# ATtiny85_and_DRV8830_Combo_--_v04.net
KiCad netlist of a schematic drawn in EAGLE
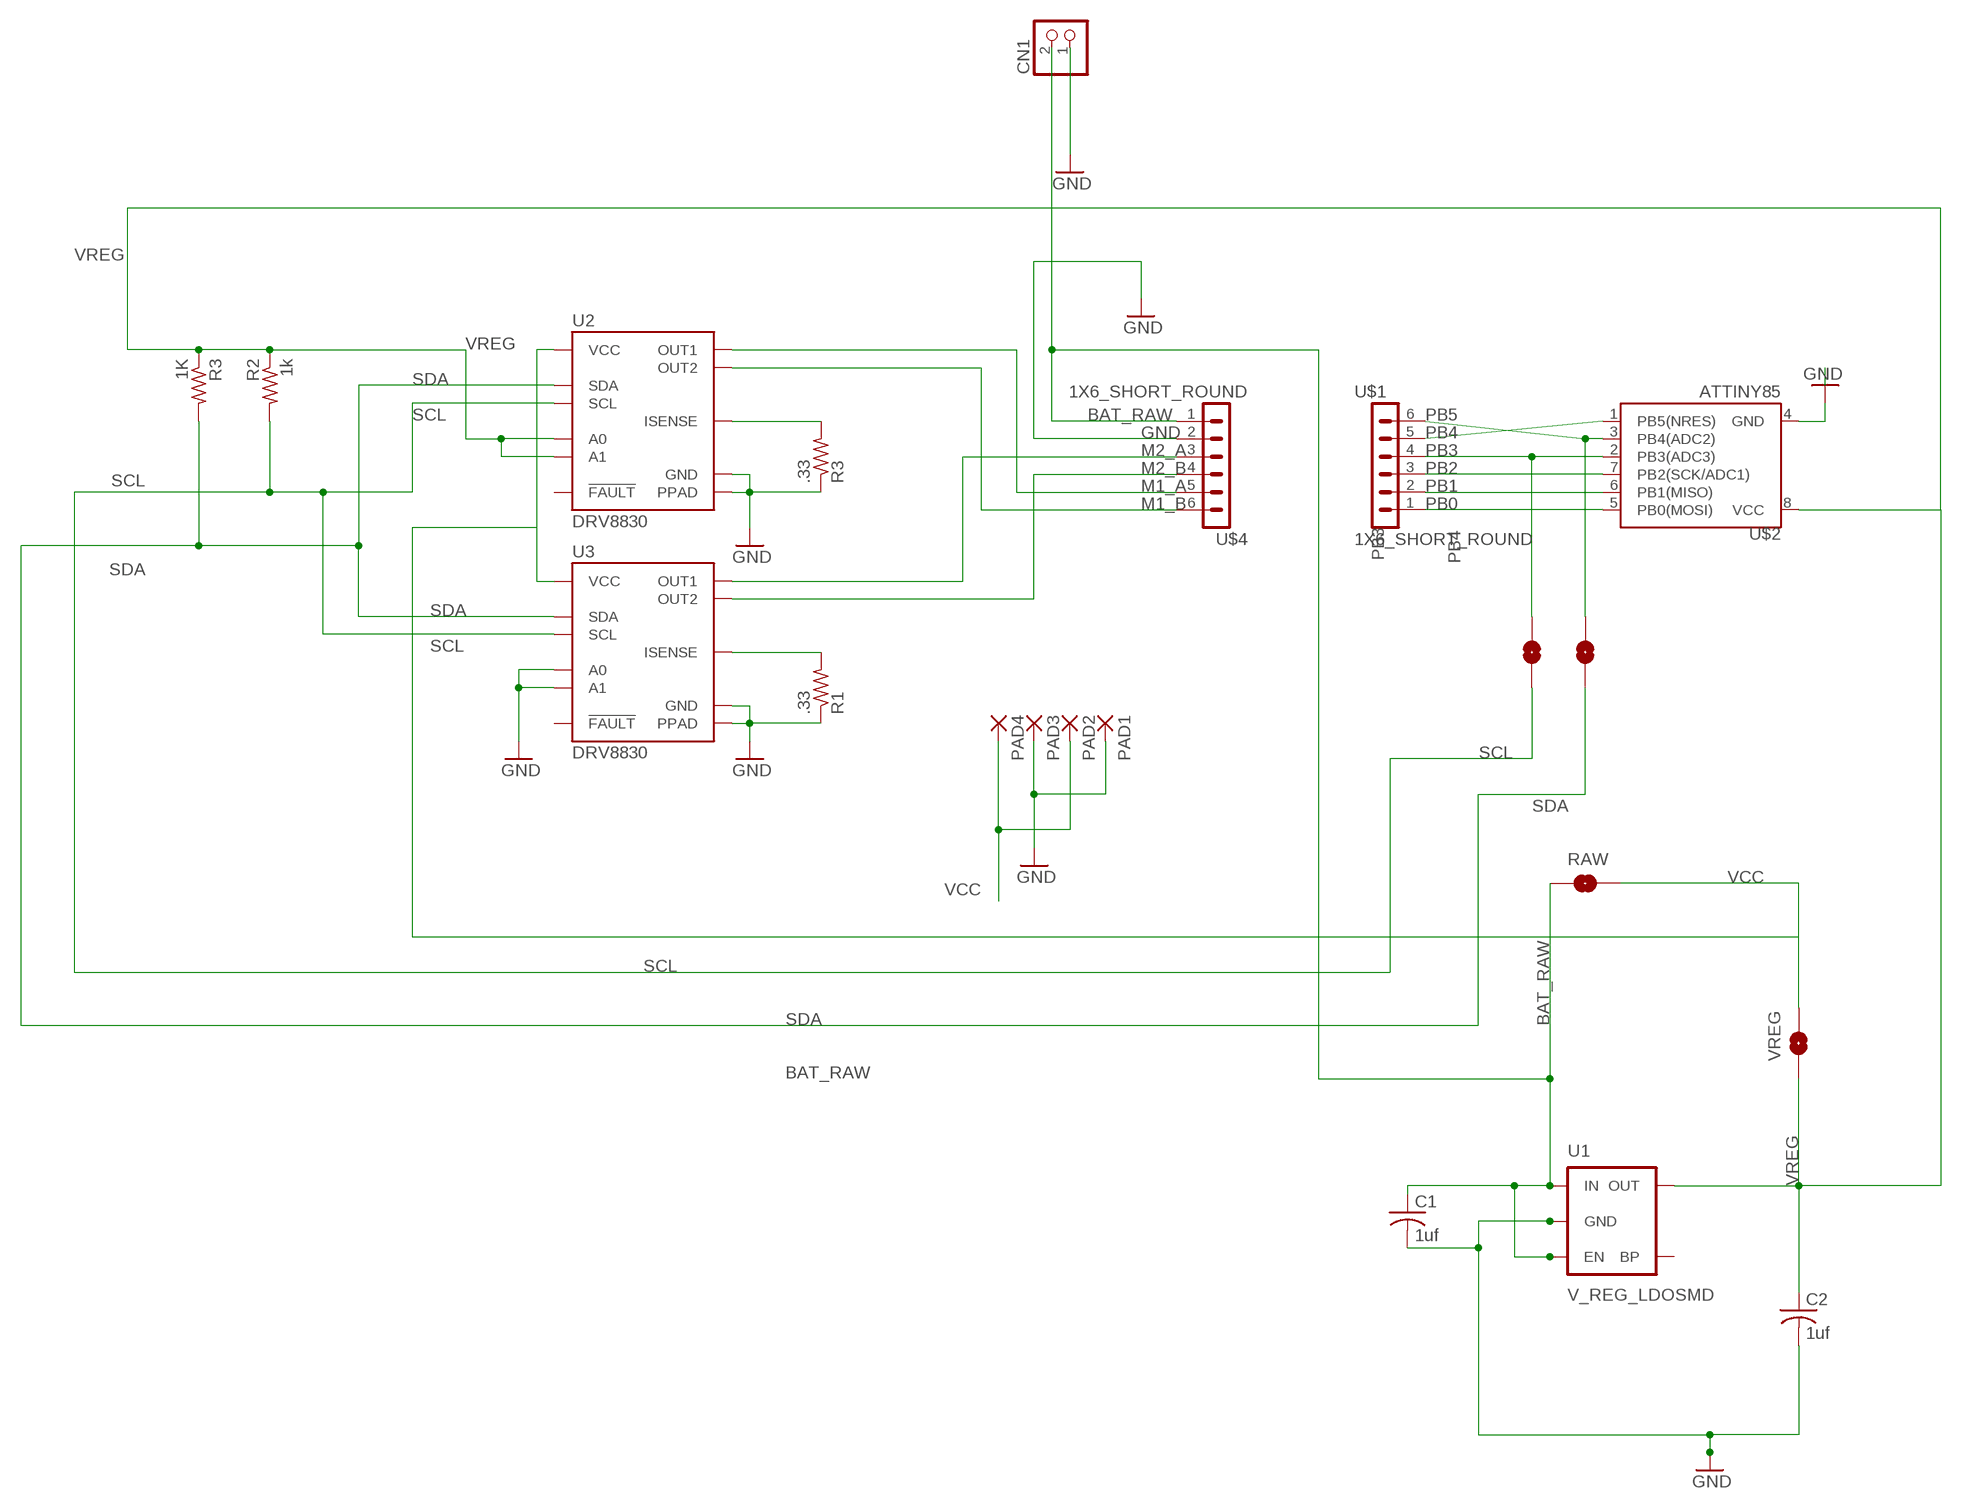
[diagram p0: schematic, sheet 1]

(export (version "E")
  (design (tool "Eeschema 10.0.6"))
  (components
    (comp (ref "1K")
      (value "R3")
      (footprint "eagle-import:R0402")
      (libsource (lib "eagle-import") (part "R-US_R0402"))
    )
    (comp (ref "C1")
      (value "1uf")
      (footprint "eagle-import:C0402")
      (libsource (lib "eagle-import") (part "C-USC0402"))
    )
    (comp (ref "C2")
      (value "1uf")
      (footprint "eagle-import:C0402")
      (libsource (lib "eagle-import") (part "C-USC0402"))
    )
    (comp (ref "CN1")
      (value "JST_2PIN-THM")
      (footprint "eagle-import:JST-PH-2-THM")
      (libsource (lib "eagle-import") (part "JST_2PIN-THM"))
    )
    (comp (ref "PAD1")
      (value "SMD2")
      (footprint "eagle-import:SMD1,27-2,54")
      (libsource (lib "eagle-import") (part "SMD2"))
    )
    (comp (ref "PAD2")
      (value "SMD2")
      (footprint "eagle-import:SMD1,27-2,54")
      (libsource (lib "eagle-import") (part "SMD2"))
    )
    (comp (ref "PAD3")
      (value "SMD2")
      (footprint "eagle-import:SMD1,27-2,54")
      (libsource (lib "eagle-import") (part "SMD2"))
    )
    (comp (ref "PAD4")
      (value "SMD2")
      (footprint "eagle-import:SMD1,27-2,54")
      (libsource (lib "eagle-import") (part "SMD2"))
    )
    (comp (ref "R1")
      (value ".33")
      (footprint "eagle-import:R0402")
      (libsource (lib "eagle-import") (part "R-US_R0402"))
    )
    (comp (ref "R2")
      (value "1k")
      (footprint "eagle-import:R0402")
      (libsource (lib "eagle-import") (part "R-US_R0402"))
    )
    (comp (ref "R3")
      (value ".33")
      (footprint "eagle-import:R0402")
      (libsource (lib "eagle-import") (part "R-US_R0402"))
    )
    (comp (ref "RAW")
      (value "SOLDERJUMPERNO")
      (footprint "eagle-import:SJ_2S-NO")
      (libsource (lib "eagle-import") (part "SOLDERJUMPERNO"))
    )
    (comp (ref "SJ6")
      (value "SOLDERJUMPERNO")
      (footprint "eagle-import:SJ_2S-NO")
      (libsource (lib "eagle-import") (part "SOLDERJUMPERNO"))
    )
    (comp (ref "SJ7")
      (value "SOLDERJUMPERNO")
      (footprint "eagle-import:SJ_2S-NO")
      (libsource (lib "eagle-import") (part "SOLDERJUMPERNO"))
    )
    (comp (ref "U$1")
      (value "1X6_SHORT_ROUND")
      (footprint "eagle-import:1X6_SHORT_ROUND")
      (libsource (lib "eagle-import") (part "1X6_SHORT_ROUND"))
    )
    (comp (ref "U$2")
      (value "ATTINY85")
      (footprint "eagle-import:SO08-EIAJ")
      (libsource (lib "eagle-import") (part "ATTINY45"))
    )
    (comp (ref "U$4")
      (value "1X6_SHORT_ROUND")
      (footprint "eagle-import:1X6_SHORT_ROUND")
      (libsource (lib "eagle-import") (part "1X6_SHORT_ROUND"))
    )
    (comp (ref "U1")
      (value "V_REG_LDOSMD")
      (footprint "eagle-import:SOT23-5")
      (libsource (lib "eagle-import") (part "V_REG_LDOSMD"))
    )
    (comp (ref "U2")
      (value "DRV8830")
      (footprint "eagle-import:MSOP-10-GNDPAD")
      (libsource (lib "eagle-import") (part "DRV8830"))
    )
    (comp (ref "U3")
      (value "DRV8830")
      (footprint "eagle-import:MSOP-10-GNDPAD")
      (libsource (lib "eagle-import") (part "DRV8830"))
    )
    (comp (ref "VREG")
      (value "SOLDERJUMPERNO")
      (footprint "eagle-import:SJ_2S-NO")
      (libsource (lib "eagle-import") (part "SOLDERJUMPERNO"))
    )
  )
  (nets
    (net (code "1") (name "/BAT_RAW") (class "Default")
      (node (ref "C1") (pin "1") (pinfunction "1_1") (pintype "passive"))
      (node (ref "CN1") (pin "2") (pinfunction "1_2") (pintype "passive"))
      (node (ref "RAW") (pin "1") (pinfunction "1_1") (pintype "passive"))
      (node (ref "U$4") (pin "1") (pinfunction "1_1") (pintype "passive"))
      (node (ref "U1") (pin "1") (pinfunction "IN_1") (pintype "input"))
      (node (ref "U1") (pin "3") (pinfunction "EN_3") (pintype "input"))
    )
    (net (code "2") (name "/M1_A") (class "Default")
      (node (ref "U$4") (pin "5") (pinfunction "5_5") (pintype "passive"))
      (node (ref "U2") (pin "3") (pinfunction "OUT1_3") (pintype "power_in"))
    )
    (net (code "3") (name "/M1_B") (class "Default")
      (node (ref "U$4") (pin "6") (pinfunction "6_6") (pintype "passive"))
      (node (ref "U2") (pin "1") (pinfunction "OUT2_1") (pintype "power_in"))
    )
    (net (code "4") (name "/M2_A") (class "Default")
      (node (ref "U$4") (pin "3") (pinfunction "3_3") (pintype "passive"))
      (node (ref "U3") (pin "3") (pinfunction "OUT1_3") (pintype "power_in"))
    )
    (net (code "5") (name "/M2_B") (class "Default")
      (node (ref "U$4") (pin "4") (pinfunction "4_4") (pintype "passive"))
      (node (ref "U3") (pin "1") (pinfunction "OUT2_1") (pintype "power_in"))
    )
    (net (code "6") (name "/PB0") (class "Default")
      (node (ref "U$1") (pin "1") (pinfunction "1_1") (pintype "passive"))
      (node (ref "U$2") (pin "5") (pinfunction "PB0(MOSI)_5") (pintype "bidirectional"))
    )
    (net (code "7") (name "/PB1") (class "Default")
      (node (ref "U$1") (pin "2") (pinfunction "2_2") (pintype "passive"))
      (node (ref "U$2") (pin "6") (pinfunction "PB1(MISO)_6") (pintype "bidirectional"))
    )
    (net (code "8") (name "/PB2") (class "Default")
      (node (ref "U$1") (pin "3") (pinfunction "3_3") (pintype "passive"))
      (node (ref "U$2") (pin "7") (pinfunction "PB2(SCK/ADC1)_7") (pintype "bidirectional"))
    )
    (net (code "9") (name "/PB3") (class "Default")
      (node (ref "SJ7") (pin "2") (pinfunction "2_2") (pintype "passive"))
      (node (ref "U$1") (pin "4") (pinfunction "4_4") (pintype "passive"))
      (node (ref "U$2") (pin "2") (pinfunction "PB3(ADC3)_2") (pintype "bidirectional"))
    )
    (net (code "10") (name "/PB4") (class "Default")
      (node (ref "SJ6") (pin "2") (pinfunction "2_2") (pintype "passive"))
      (node (ref "U$1") (pin "6") (pinfunction "6_6") (pintype "passive"))
      (node (ref "U$2") (pin "3") (pinfunction "PB4(ADC2)_3") (pintype "bidirectional"))
    )
    (net (code "11") (name "/PB5") (class "Default")
      (node (ref "U$1") (pin "5") (pinfunction "5_5") (pintype "passive"))
      (node (ref "U$2") (pin "1") (pinfunction "PB5(NRES)_1") (pintype "bidirectional"))
    )
    (net (code "12") (name "/SCL") (class "Default")
      (node (ref "R2") (pin "2") (pinfunction "2_2") (pintype "passive"))
      (node (ref "SJ7") (pin "1") (pinfunction "1_1") (pintype "passive"))
      (node (ref "U2") (pin "10") (pinfunction "SCL_10") (pintype "input"))
      (node (ref "U3") (pin "10") (pinfunction "SCL_10") (pintype "input"))
    )
    (net (code "13") (name "/SDA") (class "Default")
      (node (ref "1K") (pin "2") (pinfunction "2_2") (pintype "passive"))
      (node (ref "SJ6") (pin "1") (pinfunction "1_1") (pintype "passive"))
      (node (ref "U2") (pin "9") (pinfunction "SDA_9") (pintype "bidirectional"))
      (node (ref "U3") (pin "9") (pinfunction "SDA_9") (pintype "bidirectional"))
    )
    (net (code "14") (name "/VCC") (class "Default")
      (node (ref "PAD2") (pin "1") (pinfunction "P_1") (pintype "passive"))
      (node (ref "PAD4") (pin "1") (pinfunction "P_1") (pintype "passive"))
      (node (ref "RAW") (pin "2") (pinfunction "2_2") (pintype "passive"))
      (node (ref "U2") (pin "4") (pinfunction "VCC_4") (pintype "power_in"))
      (node (ref "U3") (pin "4") (pinfunction "VCC_4") (pintype "power_in"))
      (node (ref "VREG") (pin "2") (pinfunction "2_2") (pintype "passive"))
    )
    (net (code "15") (name "/VREG") (class "Default")
      (node (ref "1K") (pin "1") (pinfunction "1_1") (pintype "passive"))
      (node (ref "C2") (pin "1") (pinfunction "1_1") (pintype "passive"))
      (node (ref "R2") (pin "1") (pinfunction "1_1") (pintype "passive"))
      (node (ref "U$2") (pin "8") (pinfunction "VCC_8") (pintype "bidirectional"))
      (node (ref "U1") (pin "5") (pinfunction "OUT_5") (pintype "passive"))
      (node (ref "U2") (pin "7") (pinfunction "A0_7") (pintype "input"))
      (node (ref "U2") (pin "8") (pinfunction "A1_8") (pintype "input"))
      (node (ref "VREG") (pin "1") (pinfunction "1_1") (pintype "passive"))
    )
    (net (code "16") (name "GND") (class "Default")
      (node (ref "C1") (pin "2") (pinfunction "2_2") (pintype "passive"))
      (node (ref "C2") (pin "2") (pinfunction "2_2") (pintype "passive"))
      (node (ref "CN1") (pin "1") (pinfunction "2_1") (pintype "passive"))
      (node (ref "PAD1") (pin "1") (pinfunction "P_1") (pintype "passive"))
      (node (ref "PAD3") (pin "1") (pinfunction "P_1") (pintype "passive"))
      (node (ref "R1") (pin "1") (pinfunction "1_1") (pintype "passive"))
      (node (ref "R3") (pin "1") (pinfunction "1_1") (pintype "passive"))
      (node (ref "U$2") (pin "4") (pinfunction "GND_4") (pintype "bidirectional"))
      (node (ref "U$4") (pin "2") (pinfunction "2_2") (pintype "passive"))
      (node (ref "U1") (pin "2") (pinfunction "GND_2") (pintype "input"))
      (node (ref "U2") (pin "5") (pinfunction "GND_5") (pintype "power_in"))
      (node (ref "U2") (pin "GND") (pinfunction "PPAD_GND") (pintype "power_in"))
      (node (ref "U3") (pin "5") (pinfunction "GND_5") (pintype "power_in"))
      (node (ref "U3") (pin "7") (pinfunction "A0_7") (pintype "input"))
      (node (ref "U3") (pin "8") (pinfunction "A1_8") (pintype "input"))
      (node (ref "U3") (pin "GND") (pinfunction "PPAD_GND") (pintype "power_in"))
    )
    (net (code "17") (name "Net-(U2-ISENSE)") (class "Default")
      (node (ref "R3") (pin "2") (pinfunction "2_2") (pintype "passive"))
      (node (ref "U2") (pin "2") (pinfunction "ISENSE_2") (pintype "bidirectional"))
    )
    (net (code "18") (name "Net-(U3-ISENSE)") (class "Default")
      (node (ref "R1") (pin "2") (pinfunction "2_2") (pintype "passive"))
      (node (ref "U3") (pin "2") (pinfunction "ISENSE_2") (pintype "bidirectional"))
    )
    (net (code "19") (name "unconnected-(U1-BP-Pad4)") (class "Default")
      (node (ref "U1") (pin "4") (pinfunction "BP_4") (pintype "input"))
    )
    (net (code "20") (name "unconnected-(U2-~{FAULT}-Pad6)") (class "Default")
      (node (ref "U2") (pin "6") (pinfunction "~{FAULT}_6") (pintype "output"))
    )
    (net (code "21") (name "unconnected-(U3-~{FAULT}-Pad6)") (class "Default")
      (node (ref "U3") (pin "6") (pinfunction "~{FAULT}_6") (pintype "output"))
    )
  )
)
